# ANA_FE_CLK_SYNTH.net
KiCad netlist of a schematic drawn in Altium Designer
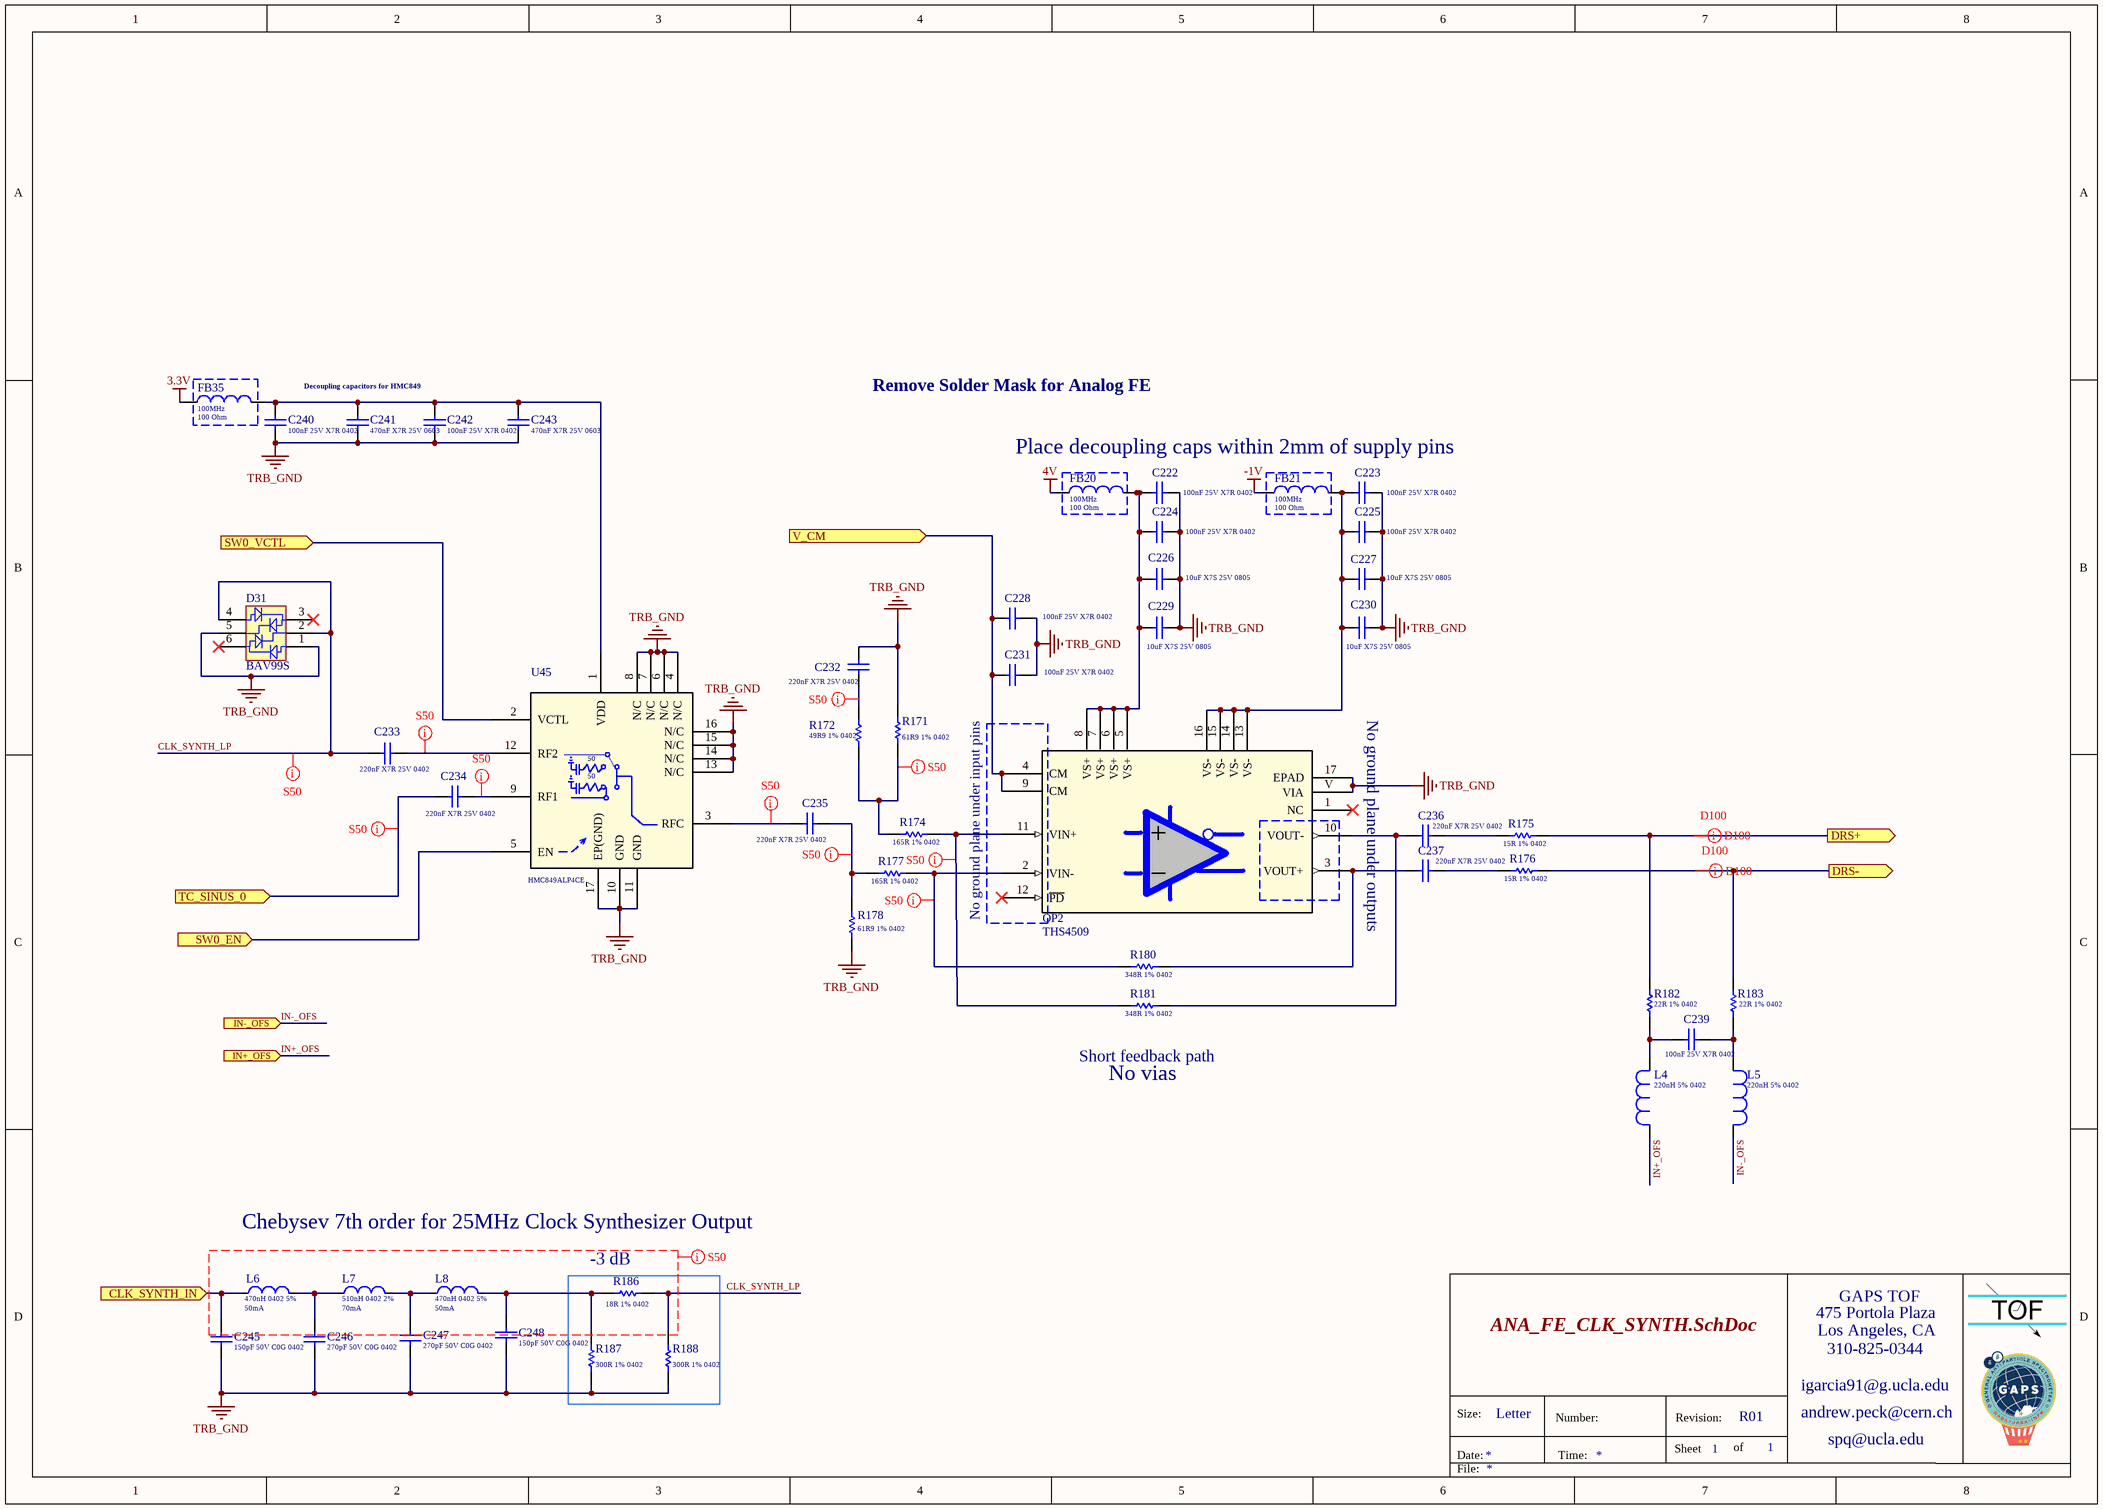
[diagram p0: ANA_FE_CLK_SYNTH.SchDoc]

(export (version "E")
  (design (tool "Eeschema 10.0.6"))
  (components
    (comp (ref "C222")
      (value "Cap_Taiyo_Yuden_TMK105B7104KV-FR_100nF")
      (footprint "Cap_Taiyo_Yuden_TMK105B7104KV-FR_100nF")
      (description "CAP CER 100nF 25V X7R 0402")
      (fields (field (name "CAPACITANCE") "100nF 25V X7R 0402"))
      (libsource (lib "Cap_Taiyo_Yuden_TMK105B7104KV-FR_100nF") (part "Cap_Taiyo_Yuden_TMK105B7104KV-FR_100nF"))
    )
    (comp (ref "C223")
      (value "Cap_Taiyo_Yuden_TMK105B7104KV-FR_100nF")
      (footprint "Cap_Taiyo_Yuden_TMK105B7104KV-FR_100nF")
      (description "CAP CER 100nF 25V X7R 0402")
      (fields (field (name "CAPACITANCE") "100nF 25V X7R 0402"))
      (libsource (lib "Cap_Taiyo_Yuden_TMK105B7104KV-FR_100nF") (part "Cap_Taiyo_Yuden_TMK105B7104KV-FR_100nF"))
    )
    (comp (ref "C224")
      (value "Cap_Taiyo_Yuden_TMK105B7104KV-FR_100nF")
      (footprint "Cap_Taiyo_Yuden_TMK105B7104KV-FR_100nF")
      (description "CAP CER 100nF 25V X7R 0402")
      (fields (field (name "CAPACITANCE") "100nF 25V X7R 0402"))
      (libsource (lib "Cap_Taiyo_Yuden_TMK105B7104KV-FR_100nF") (part "Cap_Taiyo_Yuden_TMK105B7104KV-FR_100nF"))
    )
    (comp (ref "C225")
      (value "Cap_Taiyo_Yuden_TMK105B7104KV-FR_100nF")
      (footprint "Cap_Taiyo_Yuden_TMK105B7104KV-FR_100nF")
      (description "CAP CER 100nF 25V X7R 0402")
      (fields (field (name "CAPACITANCE") "100nF 25V X7R 0402"))
      (libsource (lib "Cap_Taiyo_Yuden_TMK105B7104KV-FR_100nF") (part "Cap_Taiyo_Yuden_TMK105B7104KV-FR_100nF"))
    )
    (comp (ref "C226")
      (value "Cap_Murata_ GRM21BC71E106ME11L_10uF")
      (footprint "Cap_Murata_ GRM21BC71E106ME11L_10uF")
      (description "CAP CER 10uF 25V X7R 0805")
      (fields (field (name "CAPACITANCE") "10uF X7S 25V 0805"))
      (libsource (lib "Cap_Murata_ GRM21BC71E106ME11L_10uF") (part "Cap_Murata_ GRM21BC71E106ME11L_10uF"))
    )
    (comp (ref "C227")
      (value "Cap_Murata_ GRM21BC71E106ME11L_10uF")
      (footprint "Cap_Murata_ GRM21BC71E106ME11L_10uF")
      (description "CAP CER 10uF 25V X7R 0805")
      (fields (field (name "CAPACITANCE") "10uF X7S 25V 0805"))
      (libsource (lib "Cap_Murata_ GRM21BC71E106ME11L_10uF") (part "Cap_Murata_ GRM21BC71E106ME11L_10uF"))
    )
    (comp (ref "C228")
      (value "Cap_Taiyo_Yuden_TMK105B7104KV-FR_100nF")
      (footprint "Cap_Taiyo_Yuden_TMK105B7104KV-FR_100nF")
      (description "CAP CER 100nF 25V X7R 0402")
      (fields (field (name "CAPACITANCE") "100nF 25V X7R 0402"))
      (libsource (lib "Cap_Taiyo_Yuden_TMK105B7104KV-FR_100nF") (part "Cap_Taiyo_Yuden_TMK105B7104KV-FR_100nF"))
    )
    (comp (ref "C229")
      (value "Cap_Murata_ GRM21BC71E106ME11L_10uF")
      (footprint "Cap_Murata_ GRM21BC71E106ME11L_10uF")
      (description "CAP CER 10uF 25V X7R 0805")
      (fields (field (name "CAPACITANCE") "10uF X7S 25V 0805"))
      (libsource (lib "Cap_Murata_ GRM21BC71E106ME11L_10uF") (part "Cap_Murata_ GRM21BC71E106ME11L_10uF"))
    )
    (comp (ref "C230")
      (value "Cap_Murata_ GRM21BC71E106ME11L_10uF")
      (footprint "Cap_Murata_ GRM21BC71E106ME11L_10uF")
      (description "CAP CER 10uF 25V X7R 0805")
      (fields (field (name "CAPACITANCE") "10uF X7S 25V 0805"))
      (libsource (lib "Cap_Murata_ GRM21BC71E106ME11L_10uF") (part "Cap_Murata_ GRM21BC71E106ME11L_10uF"))
    )
    (comp (ref "C231")
      (value "Cap_Taiyo_Yuden_TMK105B7104KV-FR_100nF")
      (footprint "Cap_Taiyo_Yuden_TMK105B7104KV-FR_100nF")
      (description "CAP CER 100nF 25V X7R 0402")
      (fields (field (name "CAPACITANCE") "100nF 25V X7R 0402"))
      (libsource (lib "Cap_Taiyo_Yuden_TMK105B7104KV-FR_100nF") (part "Cap_Taiyo_Yuden_TMK105B7104KV-FR_100nF"))
    )
    (comp (ref "C232")
      (value "Cap_TDK_C1608X5R1A106M080AC_220nF")
      (footprint "Cap_TDK_C1608X5R1A106M080AC_220nF")
      (description "CAP CER 220nF 50V X7R 0402")
      (fields (field (name "CAPACITANCE") "220nF X7R 25V 0402"))
      (libsource (lib "Cap_TDK_C1608X5R1A106M080AC_220nF") (part "Cap_TDK_C1608X5R1A106M080AC_220nF"))
    )
    (comp (ref "C233")
      (value "Cap_TDK_C1608X5R1A106M080AC_220nF")
      (footprint "Cap_TDK_C1608X5R1A106M080AC_220nF")
      (description "CAP CER 220nF 50V X7R 0402")
      (fields (field (name "CAPACITANCE") "220nF X7R 25V 0402"))
      (libsource (lib "Cap_TDK_C1608X5R1A106M080AC_220nF") (part "Cap_TDK_C1608X5R1A106M080AC_220nF"))
    )
    (comp (ref "C234")
      (value "Cap_TDK_C1608X5R1A106M080AC_220nF")
      (footprint "Cap_TDK_C1608X5R1A106M080AC_220nF")
      (description "CAP CER 220nF 50V X7R 0402")
      (fields (field (name "CAPACITANCE") "220nF X7R 25V 0402"))
      (libsource (lib "Cap_TDK_C1608X5R1A106M080AC_220nF") (part "Cap_TDK_C1608X5R1A106M080AC_220nF"))
    )
    (comp (ref "C235")
      (value "Cap_TDK_C1608X5R1A106M080AC_220nF")
      (footprint "Cap_TDK_C1608X5R1A106M080AC_220nF")
      (description "CAP CER 220nF 50V X7R 0402")
      (fields (field (name "CAPACITANCE") "220nF X7R 25V 0402"))
      (libsource (lib "Cap_TDK_C1608X5R1A106M080AC_220nF") (part "Cap_TDK_C1608X5R1A106M080AC_220nF"))
    )
    (comp (ref "C236")
      (value "Cap_TDK_C1608X5R1A106M080AC_220nF")
      (footprint "Cap_TDK_C1608X5R1A106M080AC_220nF")
      (description "CAP CER 220nF 50V X7R 0402")
      (fields (field (name "CAPACITANCE") "220nF X7R 25V 0402"))
      (libsource (lib "Cap_TDK_C1608X5R1A106M080AC_220nF") (part "Cap_TDK_C1608X5R1A106M080AC_220nF"))
    )
    (comp (ref "C237")
      (value "Cap_TDK_C1608X5R1A106M080AC_220nF")
      (footprint "Cap_TDK_C1608X5R1A106M080AC_220nF")
      (description "CAP CER 220nF 50V X7R 0402")
      (fields (field (name "CAPACITANCE") "220nF X7R 25V 0402"))
      (libsource (lib "Cap_TDK_C1608X5R1A106M080AC_220nF") (part "Cap_TDK_C1608X5R1A106M080AC_220nF"))
    )
    (comp (ref "C239")
      (value "Cap_Taiyo_Yuden_TMK105B7104KV-FR_100nF")
      (footprint "Cap_Taiyo_Yuden_TMK105B7104KV-FR_100nF")
      (description "CAP CER 100nF 25V X7R 0402")
      (fields (field (name "CAPACITANCE") "100nF 25V X7R 0402"))
      (libsource (lib "Cap_Taiyo_Yuden_TMK105B7104KV-FR_100nF") (part "Cap_Taiyo_Yuden_TMK105B7104KV-FR_100nF"))
    )
    (comp (ref "C240")
      (value "Cap_Taiyo_Yuden_TMK105B7104KV-FR_100nF")
      (footprint "Cap_Taiyo_Yuden_TMK105B7104KV-FR_100nF")
      (description "CAP CER 100nF 25V X7R 0402")
      (fields (field (name "CAPACITANCE") "100nF 25V X7R 0402"))
      (libsource (lib "Cap_Taiyo_Yuden_TMK105B7104KV-FR_100nF") (part "Cap_Taiyo_Yuden_TMK105B7104KV-FR_100nF"))
    )
    (comp (ref "C241")
      (value "Cap_Wurth_Electronics_885012206075_470nF")
      (footprint "Cap_Wurth_Electronics_885012206075_470nF")
      (description "CAP CER 470nF 25V X7R 0603")
      (fields (field (name "CAPACITANCE") "470nF X7R 25V 0603"))
      (libsource (lib "Cap_Wurth_Electronics_885012206075_470nF") (part "Cap_Wurth_Electronics_885012206075_470nF"))
    )
    (comp (ref "C242")
      (value "Cap_Taiyo_Yuden_TMK105B7104KV-FR_100nF")
      (footprint "Cap_Taiyo_Yuden_TMK105B7104KV-FR_100nF")
      (description "CAP CER 100nF 25V X7R 0402")
      (fields (field (name "CAPACITANCE") "100nF 25V X7R 0402"))
      (libsource (lib "Cap_Taiyo_Yuden_TMK105B7104KV-FR_100nF") (part "Cap_Taiyo_Yuden_TMK105B7104KV-FR_100nF"))
    )
    (comp (ref "C243")
      (value "Cap_Wurth_Electronics_885012206075_470nF")
      (footprint "Cap_Wurth_Electronics_885012206075_470nF")
      (description "CAP CER 470nF 25V X7R 0603")
      (fields (field (name "CAPACITANCE") "470nF X7R 25V 0603"))
      (libsource (lib "Cap_Wurth_Electronics_885012206075_470nF") (part "Cap_Wurth_Electronics_885012206075_470nF"))
    )
    (comp (ref "C245")
      (value "Cap_TDK_CGA2B2C0G2A151J050BE_150pF")
      (footprint "Cap_TDK_CGA2B2C0G2A151J050BE_150pF")
      (description "CAP 150pF 50V C0G ±1% 0402 (1000 Metric) Thickness 1mm SMD")
      (fields (field (name "CAPACITANCE") "150pF 50V C0G 0402"))
      (libsource (lib "Cap_TDK_CGA2B2C0G2A151J050BE_150pF") (part "Cap_TDK_CGA2B2C0G2A151J050BE_150pF"))
    )
    (comp (ref "C246")
      (value "Cap_Murata_GCM1555C1H271FA16D_270pF")
      (footprint "Cap_Murata_GCM1555C1H271FA16D_270pF")
      (description "CAP 270pF 50V C0G ±1% 0402")
      (fields (field (name "CAPACITANCE") "270pF 50V C0G 0402"))
      (libsource (lib "Cap_Murata_GCM1555C1H271FA16D_270pF") (part "Cap_Murata_GCM1555C1H271FA16D_270pF"))
    )
    (comp (ref "C247")
      (value "Cap_Murata_GCM1555C1H271FA16D_270pF")
      (footprint "Cap_Murata_GCM1555C1H271FA16D_270pF")
      (description "CAP 270pF 50V C0G ±1% 0402")
      (fields (field (name "CAPACITANCE") "270pF 50V C0G 0402"))
      (libsource (lib "Cap_Murata_GCM1555C1H271FA16D_270pF") (part "Cap_Murata_GCM1555C1H271FA16D_270pF"))
    )
    (comp (ref "C248")
      (value "Cap_TDK_CGA2B2C0G2A151J050BE_150pF")
      (footprint "Cap_TDK_CGA2B2C0G2A151J050BE_150pF")
      (description "CAP 150pF 50V C0G ±1% 0402 (1000 Metric) Thickness 1mm SMD")
      (fields (field (name "CAPACITANCE") "150pF 50V C0G 0402"))
      (libsource (lib "Cap_TDK_CGA2B2C0G2A151J050BE_150pF") (part "Cap_TDK_CGA2B2C0G2A151J050BE_150pF"))
    )
    (comp (ref "D31")
      (value "BAV99S")
      (footprint "INF-SOT363_V")
      (description "Silicon Switching Diode, SOT363, Reel, Green")
      (fields (field (name "MANUFACTURER") "Infineon"))
      (libsource (lib "Altium Content Vault") (part "INF-D_A1K2C3A4K5C6-6"))
    )
    (comp (ref "FB20")
      (value "742792731")
      (footprint "FB_Wurth_Electronics_742792731_100Ohms")
      (description "FB SMD 100 OHM 25% 1.2A 0402")
      (fields (field (name "MEASURING FREQUENCY") "100MHz") (field (name "IMPEDANCE") "100 Ohm"))
      (libsource (lib "FB_Wurth_Electronics_742792731_100Ohms") (part "FB_Wurth_Electronics_742792731_100Ohms"))
    )
    (comp (ref "FB21")
      (value "742792731")
      (footprint "FB_Wurth_Electronics_742792731_100Ohms")
      (description "FB SMD 100 OHM 25% 1.2A 0402")
      (fields (field (name "MEASURING FREQUENCY") "100MHz") (field (name "IMPEDANCE") "100 Ohm"))
      (libsource (lib "FB_Wurth_Electronics_742792731_100Ohms") (part "FB_Wurth_Electronics_742792731_100Ohms"))
    )
    (comp (ref "FB35")
      (value "742792731")
      (footprint "FB_Wurth_Electronics_742792731_100Ohms")
      (description "FB SMD 100 OHM 25% 1.2A 0402")
      (fields (field (name "MEASURING FREQUENCY") "100MHz") (field (name "IMPEDANCE") "100 Ohm"))
      (libsource (lib "FB_Wurth_Electronics_742792731_100Ohms") (part "FB_Wurth_Electronics_742792731_100Ohms"))
    )
    (comp (ref "L4")
      (value "Ind_TDK_ MLG1005SR22JT000_220nH")
      (footprint "Ind_TDK_ MLG1005SR22JT000_220nH")
      (description "Fixed Inductors .22 UH 5%")
      (fields (field (name "INDUCTANCE") "220nH 5% 0402"))
      (libsource (lib "Ind_TDK_ MLG1005SR22JT000_220nH") (part "Ind_TDK_ MLG1005SR22JT000_220nH"))
    )
    (comp (ref "L5")
      (value "Ind_TDK_ MLG1005SR22JT000_220nH")
      (footprint "Ind_TDK_ MLG1005SR22JT000_220nH")
      (description "Fixed Inductors .22 UH 5%")
      (fields (field (name "INDUCTANCE") "220nH 5% 0402"))
      (libsource (lib "Ind_TDK_ MLG1005SR22JT000_220nH") (part "Ind_TDK_ MLG1005SR22JT000_220nH"))
    )
    (comp (ref "L6")
      (value "470nH 0402 5%")
      (footprint "TDK_MLF1005GR47JT000_0")
      (description "IND 470nH Shielded Multilayer Inductor 50mA 420 mOhm Max 0402 (1005 Metric)")
      (fields
        (field (name "PART NUMBER") "MLF1005GR47JT000")
        (field (name "MANUFACTURER") "TDK")
        (field (name "CURRENT RATING") "50mA")
      )
      (libsource (lib "Ind_TDK_MLF1005GR47JT000_470nH") (part "Ind_TDK_MLF1005GR47JT000"))
    )
    (comp (ref "L7")
      (value "510nH 0402 2%")
      (footprint "TDK_MHQ1005PR51GT000_0")
      (description "IND 510nH Shielded Multilayer Inductor 70mA 10.2 Ohm Max 0402 (1005 Metric)")
      (fields
        (field (name "PART NUMBER") "MHQ1005PR51GT000")
        (field (name "MANUFACTURER") "TDK")
        (field (name "CURRENT RATING") "70mA")
      )
      (libsource (lib "Ind_TDK_MHQ1005PR51GT000_510nH") (part "Ind_TDK_MHQ1005PR51GT000"))
    )
    (comp (ref "L8")
      (value "470nH 0402 5%")
      (footprint "TDK_MLF1005GR47JT000_0")
      (description "IND 470nH Shielded Multilayer Inductor 50mA 420 mOhm Max 0402 (1005 Metric)")
      (fields
        (field (name "PART NUMBER") "MLF1005GR47JT000")
        (field (name "MANUFACTURER") "TDK")
        (field (name "CURRENT RATING") "50mA")
      )
      (libsource (lib "Ind_TDK_MLF1005GR47JT000_470nH") (part "Ind_TDK_MLF1005GR47JT000"))
    )
    (comp (ref "OP2")
      (value "THS4509")
      (footprint "RGT16")
      (description "Imported")
      (fields (field (name "MANUFACTURER_PART_NUMBER") "THS4509RGTT"))
      (libsource (lib "THS4509RGTT") (part "THS4509RGTT"))
    )
    (comp (ref "R171")
      (value "61R9 1% 0402")
      (footprint "RESC0402(1005)_L")
      (description "61R9 0.063W 1% 0402 (1005 Metric)  SMD")
      (fields (field (name "TOLERANCE") "1 %") (field (name "POWER") "0.063 W"))
      (libsource (lib "Altium Content Vault") (part "RES"))
    )
    (comp (ref "R172")
      (value "49R9 1% 0402")
      (footprint "RESC0402(1005)_L")
      (description "49R9 0.063W 1% 0402 (1005 Metric)  SMD")
      (fields (field (name "POWER") "0.063 W") (field (name "TOLERANCE") "1 %"))
      (libsource (lib "Altium Content Vault") (part "RES"))
    )
    (comp (ref "R174")
      (value "165R 1% 0402")
      (footprint "RESC0402(1005)_L")
      (description "165R 0.063W 1% 0402 (1005 Metric)  SMD")
      (fields (field (name "POWER") "0.063 W") (field (name "TOLERANCE") "1 %"))
      (libsource (lib "Altium Content Vault") (part "RES"))
    )
    (comp (ref "R175")
      (value "15R 1% 0402")
      (footprint "RESC0402(1005)_L")
      (description "15R 0.063W 1% 0402 (1005 Metric)  SMD")
      (fields (field (name "TOLERANCE") "1 %") (field (name "POWER") "0.063 W"))
      (libsource (lib "Altium Content Vault") (part "RES"))
    )
    (comp (ref "R176")
      (value "15R 1% 0402")
      (footprint "RESC0402(1005)_L")
      (description "15R 0.063W 1% 0402 (1005 Metric)  SMD")
      (fields (field (name "TOLERANCE") "1 %") (field (name "POWER") "0.063 W"))
      (libsource (lib "Altium Content Vault") (part "RES"))
    )
    (comp (ref "R177")
      (value "165R 1% 0402")
      (footprint "RESC0402(1005)_L")
      (description "165R 0.063W 1% 0402 (1005 Metric)  SMD")
      (fields (field (name "POWER") "0.063 W") (field (name "TOLERANCE") "1 %"))
      (libsource (lib "Altium Content Vault") (part "RES"))
    )
    (comp (ref "R178")
      (value "61R9 1% 0402")
      (footprint "RESC0402(1005)_L")
      (description "61R9 0.063W 1% 0402 (1005 Metric)  SMD")
      (fields (field (name "TOLERANCE") "1 %") (field (name "POWER") "0.063 W"))
      (libsource (lib "Altium Content Vault") (part "RES"))
    )
    (comp (ref "R180")
      (value "348R 1% 0402")
      (footprint "RESC0402(1005)_L")
      (description "348R 0.063W 1% 0402 (1005 Metric)  SMD")
      (fields (field (name "TOLERANCE") "1 %") (field (name "POWER") "0.063 W"))
      (libsource (lib "Altium Content Vault") (part "RES"))
    )
    (comp (ref "R181")
      (value "348R 1% 0402")
      (footprint "RESC0402(1005)_L")
      (description "348R 0.063W 1% 0402 (1005 Metric)  SMD")
      (fields (field (name "TOLERANCE") "1 %") (field (name "POWER") "0.063 W"))
      (libsource (lib "Altium Content Vault") (part "RES"))
    )
    (comp (ref "R182")
      (value "22R 1% 0402")
      (footprint "RESC0402(1005)_L")
      (description "22R 0.063W 1% 0402 (1005 Metric)  SMD")
      (fields (field (name "TOLERANCE") "1 %") (field (name "POWER") "0.063 W"))
      (libsource (lib "Altium Content Vault") (part "RES"))
    )
    (comp (ref "R183")
      (value "22R 1% 0402")
      (footprint "RESC0402(1005)_L")
      (description "22R 0.063W 1% 0402 (1005 Metric)  SMD")
      (fields (field (name "TOLERANCE") "1 %") (field (name "POWER") "0.063 W"))
      (libsource (lib "Altium Content Vault") (part "RES"))
    )
    (comp (ref "R186")
      (value "18R 1% 0402")
      (footprint "RESC0402(1005)_L")
      (description "18R 0.063W 1% 0402 (1005 Metric)  SMD")
      (fields (field (name "TOLERANCE") "1 %") (field (name "POWER") "0.063 W"))
      (libsource (lib "Altium Content Vault") (part "RES"))
    )
    (comp (ref "R187")
      (value "300R 1% 0402")
      (footprint "RESC0402(1005)_L")
      (description "300R 0.063W 1% 0402 (1005 Metric)  SMD")
      (fields (field (name "TOLERANCE") "1 %") (field (name "POWER") "0.063 W"))
      (libsource (lib "Altium Content Vault") (part "RES"))
    )
    (comp (ref "R188")
      (value "300R 1% 0402")
      (footprint "RESC0402(1005)_L")
      (description "300R 0.063W 1% 0402 (1005 Metric)  SMD")
      (fields (field (name "TOLERANCE") "1 %") (field (name "POWER") "0.063 W"))
      (libsource (lib "Altium Content Vault") (part "RES"))
    )
    (comp (ref "U45")
      (value "HMC849")
      (footprint "CP_16_40")
      (description "RF Switch ICs DC-6 GHZ Hi Isolation Switch")
      (fields (field (name "MANUFACTURER_PART_NUMBER") "HMC849ALP4CE") (field (name "SERIES") "HMC849ALP4CE"))
      (libsource (lib "HMC849ALP4CE") (part "HMC849ALP4CE"))
    )
  )
  (nets
    (net (code "1") (name "-1V") (class "Default")
      (node (ref "FB21") (pin "1") (pinfunction "1_1") (pintype "passive"))
    )
    (net (code "2") (name "/CLK_SYNTH_IN") (class "Default")
      (node (ref "C245") (pin "2") (pinfunction "2_2") (pintype "passive"))
      (node (ref "L6") (pin "1") (pinfunction "1_1") (pintype "passive"))
    )
    (net (code "3") (name "/CLK_SYNTH_LP") (class "Default")
      (node (ref "C233") (pin "2") (pinfunction "2_2") (pintype "passive"))
      (node (ref "D31") (pin "2") (pinfunction "K2_2") (pintype "passive"))
      (node (ref "D31") (pin "4") (pinfunction "A4_4") (pintype "passive"))
      (node (ref "R186") (pin "2") (pinfunction "2_2") (pintype "passive"))
      (node (ref "R188") (pin "2") (pinfunction "2_2") (pintype "passive"))
    )
    (net (code "4") (name "/DRS+") (class "Default")
      (node (ref "R175") (pin "2") (pinfunction "2_2") (pintype "passive"))
      (node (ref "R182") (pin "2") (pinfunction "2_2") (pintype "passive"))
    )
    (net (code "5") (name "/DRS-") (class "Default")
      (node (ref "R176") (pin "2") (pinfunction "2_2") (pintype "passive"))
      (node (ref "R183") (pin "2") (pinfunction "2_2") (pintype "passive"))
    )
    (net (code "6") (name "/IN+_OFS") (class "Default")
      (node (ref "L4") (pin "2") (pinfunction "2_2") (pintype "passive"))
    )
    (net (code "7") (name "/IN-_OFS") (class "Default")
      (node (ref "L5") (pin "1") (pinfunction "1_1") (pintype "passive"))
    )
    (net (code "8") (name "/SW0_EN") (class "Default")
      (node (ref "U45") (pin "5") (pinfunction "EN_5") (pintype "passive"))
    )
    (net (code "9") (name "/SW0_VCTL") (class "Default")
      (node (ref "U45") (pin "2") (pinfunction "VCTL_2") (pintype "passive"))
    )
    (net (code "10") (name "/TC_SINUS_0") (class "Default")
      (node (ref "C234") (pin "2") (pinfunction "2_2") (pintype "passive"))
    )
    (net (code "11") (name "/V_CM") (class "Default")
      (node (ref "C228") (pin "1") (pinfunction "1_1") (pintype "passive"))
      (node (ref "C231") (pin "1") (pinfunction "1_1") (pintype "passive"))
      (node (ref "OP2") (pin "4") (pinfunction "CM_4") (pintype "passive"))
      (node (ref "OP2") (pin "9") (pinfunction "CM_9") (pintype "passive"))
    )
    (net (code "12") (name "3.3V") (class "Default")
      (node (ref "FB35") (pin "1") (pinfunction "1_1") (pintype "passive"))
    )
    (net (code "13") (name "4V") (class "Default")
      (node (ref "FB20") (pin "1") (pinfunction "1_1") (pintype "passive"))
    )
    (net (code "14") (name "Net-(C222-Pad1)") (class "Default")
      (node (ref "C222") (pin "1") (pinfunction "1_1") (pintype "passive"))
      (node (ref "C224") (pin "1") (pinfunction "1_1") (pintype "passive"))
      (node (ref "C226") (pin "2") (pinfunction "2_2") (pintype "passive"))
      (node (ref "C229") (pin "2") (pinfunction "2_2") (pintype "passive"))
      (node (ref "FB20") (pin "2") (pinfunction "2_2") (pintype "passive"))
      (node (ref "OP2") (pin "5") (pinfunction "VS+_5") (pintype "power_in"))
      (node (ref "OP2") (pin "6") (pinfunction "VS+_6") (pintype "power_in"))
      (node (ref "OP2") (pin "7") (pinfunction "VS+_7") (pintype "power_in"))
      (node (ref "OP2") (pin "8") (pinfunction "VS+_8") (pintype "power_in"))
    )
    (net (code "15") (name "Net-(C223-Pad1)") (class "Default")
      (node (ref "C223") (pin "1") (pinfunction "1_1") (pintype "passive"))
      (node (ref "C225") (pin "1") (pinfunction "1_1") (pintype "passive"))
      (node (ref "C227") (pin "2") (pinfunction "2_2") (pintype "passive"))
      (node (ref "C230") (pin "2") (pinfunction "2_2") (pintype "passive"))
      (node (ref "FB21") (pin "2") (pinfunction "2_2") (pintype "passive"))
      (node (ref "OP2") (pin "13") (pinfunction "VS-_13") (pintype "power_in"))
      (node (ref "OP2") (pin "14") (pinfunction "VS-_14") (pintype "power_in"))
      (node (ref "OP2") (pin "15") (pinfunction "VS-_15") (pintype "power_in"))
      (node (ref "OP2") (pin "16") (pinfunction "VS-_16") (pintype "power_in"))
    )
    (net (code "16") (name "Net-(C232-Pad2)") (class "Default")
      (node (ref "C232") (pin "2") (pinfunction "2_2") (pintype "passive"))
      (node (ref "R172") (pin "2") (pinfunction "2_2") (pintype "passive"))
    )
    (net (code "17") (name "Net-(C235-Pad1)") (class "Default")
      (node (ref "C235") (pin "1") (pinfunction "1_1") (pintype "passive"))
      (node (ref "R177") (pin "1") (pinfunction "1_1") (pintype "passive"))
      (node (ref "R178") (pin "2") (pinfunction "2_2") (pintype "passive"))
    )
    (net (code "18") (name "Net-(C236-Pad1)") (class "Default")
      (node (ref "C236") (pin "1") (pinfunction "1_1") (pintype "passive"))
      (node (ref "R175") (pin "1") (pinfunction "1_1") (pintype "passive"))
    )
    (net (code "19") (name "Net-(C237-Pad1)") (class "Default")
      (node (ref "C237") (pin "1") (pinfunction "1_1") (pintype "passive"))
      (node (ref "R176") (pin "1") (pinfunction "1_1") (pintype "passive"))
    )
    (net (code "20") (name "Net-(C239-Pad1)") (class "Default")
      (node (ref "C239") (pin "1") (pinfunction "1_1") (pintype "passive"))
      (node (ref "L4") (pin "1") (pinfunction "1_1") (pintype "passive"))
      (node (ref "R182") (pin "1") (pinfunction "1_1") (pintype "passive"))
    )
    (net (code "21") (name "Net-(C239-Pad2)") (class "Default")
      (node (ref "C239") (pin "2") (pinfunction "2_2") (pintype "passive"))
      (node (ref "L5") (pin "2") (pinfunction "2_2") (pintype "passive"))
      (node (ref "R183") (pin "1") (pinfunction "1_1") (pintype "passive"))
    )
    (net (code "22") (name "Net-(C246-Pad2)") (class "Default")
      (node (ref "C246") (pin "2") (pinfunction "2_2") (pintype "passive"))
      (node (ref "L6") (pin "2") (pinfunction "2_2") (pintype "passive"))
      (node (ref "L7") (pin "1") (pinfunction "1_1") (pintype "passive"))
    )
    (net (code "23") (name "Net-(C247-Pad2)") (class "Default")
      (node (ref "C247") (pin "2") (pinfunction "2_2") (pintype "passive"))
      (node (ref "L7") (pin "2") (pinfunction "2_2") (pintype "passive"))
      (node (ref "L8") (pin "1") (pinfunction "1_1") (pintype "passive"))
    )
    (net (code "24") (name "Net-(C248-Pad2)") (class "Default")
      (node (ref "C248") (pin "2") (pinfunction "2_2") (pintype "passive"))
      (node (ref "L8") (pin "2") (pinfunction "2_2") (pintype "passive"))
      (node (ref "R186") (pin "1") (pinfunction "1_1") (pintype "passive"))
      (node (ref "R187") (pin "2") (pinfunction "2_2") (pintype "passive"))
    )
    (net (code "25") (name "Net-(OP2-VIN+)") (class "Default")
      (node (ref "OP2") (pin "11") (pinfunction "VIN+_11") (pintype "input"))
      (node (ref "R174") (pin "2") (pinfunction "2_2") (pintype "passive"))
      (node (ref "R181") (pin "1") (pinfunction "1_1") (pintype "passive"))
    )
    (net (code "26") (name "Net-(OP2-VIN-)") (class "Default")
      (node (ref "OP2") (pin "2") (pinfunction "VIN-_2") (pintype "input"))
      (node (ref "R177") (pin "2") (pinfunction "2_2") (pintype "passive"))
      (node (ref "R180") (pin "1") (pinfunction "1_1") (pintype "passive"))
    )
    (net (code "27") (name "Net-(OP2-VOUT+)") (class "Default")
      (node (ref "C237") (pin "2") (pinfunction "2_2") (pintype "passive"))
      (node (ref "OP2") (pin "3") (pinfunction "VOUT+_3") (pintype "output"))
      (node (ref "R180") (pin "2") (pinfunction "2_2") (pintype "passive"))
    )
    (net (code "28") (name "Net-(OP2-VOUT-)") (class "Default")
      (node (ref "C236") (pin "2") (pinfunction "2_2") (pintype "passive"))
      (node (ref "OP2") (pin "10") (pinfunction "VOUT-_10") (pintype "output"))
      (node (ref "R181") (pin "2") (pinfunction "2_2") (pintype "passive"))
    )
    (net (code "29") (name "Net-(R171-Pad1)") (class "Default")
      (node (ref "R171") (pin "1") (pinfunction "1_1") (pintype "passive"))
      (node (ref "R172") (pin "1") (pinfunction "1_1") (pintype "passive"))
      (node (ref "R174") (pin "1") (pinfunction "1_1") (pintype "passive"))
    )
    (net (code "30") (name "Net-(U45-RF1)") (class "Default")
      (node (ref "C234") (pin "1") (pinfunction "1_1") (pintype "passive"))
      (node (ref "U45") (pin "9") (pinfunction "RF1_9") (pintype "passive"))
    )
    (net (code "31") (name "Net-(U45-RF2)") (class "Default")
      (node (ref "C233") (pin "1") (pinfunction "1_1") (pintype "passive"))
      (node (ref "U45") (pin "12") (pinfunction "RF2_12") (pintype "passive"))
    )
    (net (code "32") (name "Net-(U45-RFC)") (class "Default")
      (node (ref "C235") (pin "2") (pinfunction "2_2") (pintype "passive"))
      (node (ref "U45") (pin "3") (pinfunction "RFC_3") (pintype "passive"))
    )
    (net (code "33") (name "Net-(U45-VDD)") (class "Default")
      (node (ref "C240") (pin "2") (pinfunction "2_2") (pintype "passive"))
      (node (ref "C241") (pin "1") (pinfunction "1_1") (pintype "passive"))
      (node (ref "C242") (pin "2") (pinfunction "2_2") (pintype "passive"))
      (node (ref "C243") (pin "1") (pinfunction "1_1") (pintype "passive"))
      (node (ref "FB35") (pin "2") (pinfunction "2_2") (pintype "passive"))
      (node (ref "U45") (pin "1") (pinfunction "VDD_1") (pintype "passive"))
    )
    (net (code "34") (name "TRB_GND") (class "Default")
      (node (ref "C222") (pin "2") (pinfunction "2_2") (pintype "passive"))
      (node (ref "C223") (pin "2") (pinfunction "2_2") (pintype "passive"))
      (node (ref "C224") (pin "2") (pinfunction "2_2") (pintype "passive"))
      (node (ref "C225") (pin "2") (pinfunction "2_2") (pintype "passive"))
      (node (ref "C226") (pin "1") (pinfunction "1_1") (pintype "passive"))
      (node (ref "C227") (pin "1") (pinfunction "1_1") (pintype "passive"))
      (node (ref "C228") (pin "2") (pinfunction "2_2") (pintype "passive"))
      (node (ref "C229") (pin "1") (pinfunction "1_1") (pintype "passive"))
      (node (ref "C230") (pin "1") (pinfunction "1_1") (pintype "passive"))
      (node (ref "C231") (pin "2") (pinfunction "2_2") (pintype "passive"))
      (node (ref "C232") (pin "1") (pinfunction "1_1") (pintype "passive"))
      (node (ref "C240") (pin "1") (pinfunction "1_1") (pintype "passive"))
      (node (ref "C241") (pin "2") (pinfunction "2_2") (pintype "passive"))
      (node (ref "C242") (pin "1") (pinfunction "1_1") (pintype "passive"))
      (node (ref "C243") (pin "2") (pinfunction "2_2") (pintype "passive"))
      (node (ref "C245") (pin "1") (pinfunction "1_1") (pintype "passive"))
      (node (ref "C246") (pin "1") (pinfunction "1_1") (pintype "passive"))
      (node (ref "C247") (pin "1") (pinfunction "1_1") (pintype "passive"))
      (node (ref "C248") (pin "1") (pinfunction "1_1") (pintype "passive"))
      (node (ref "D31") (pin "1") (pinfunction "A1_1") (pintype "passive"))
      (node (ref "D31") (pin "5") (pinfunction "K5_5") (pintype "passive"))
      (node (ref "OP2") (pin "17") (pinfunction "EPAD_17") (pintype "passive"))
      (node (ref "OP2") (pin "V") (pinfunction "VIA_V") (pintype "passive"))
      (node (ref "R171") (pin "2") (pinfunction "2_2") (pintype "passive"))
      (node (ref "R178") (pin "1") (pinfunction "1_1") (pintype "passive"))
      (node (ref "R187") (pin "1") (pinfunction "1_1") (pintype "passive"))
      (node (ref "R188") (pin "1") (pinfunction "1_1") (pintype "passive"))
      (node (ref "U45") (pin "10") (pinfunction "GND_10") (pintype "passive"))
      (node (ref "U45") (pin "11") (pinfunction "GND_11") (pintype "passive"))
      (node (ref "U45") (pin "13") (pinfunction "N/C_13") (pintype "passive"))
      (node (ref "U45") (pin "14") (pinfunction "N/C_14") (pintype "passive"))
      (node (ref "U45") (pin "15") (pinfunction "N/C_15") (pintype "passive"))
      (node (ref "U45") (pin "16") (pinfunction "N/C_16") (pintype "passive"))
      (node (ref "U45") (pin "17") (pinfunction "EP(GND)_17") (pintype "passive"))
      (node (ref "U45") (pin "4") (pinfunction "N/C_4") (pintype "passive"))
      (node (ref "U45") (pin "6") (pinfunction "N/C_6") (pintype "passive"))
      (node (ref "U45") (pin "7") (pinfunction "N/C_7") (pintype "passive"))
      (node (ref "U45") (pin "8") (pinfunction "N/C_8") (pintype "passive"))
    )
    (net (code "35") (name "unconnected-(D31-C3-Pad3)") (class "Default")
      (node (ref "D31") (pin "3") (pinfunction "C3_3") (pintype "passive+no_connect"))
    )
    (net (code "36") (name "unconnected-(D31-C6-Pad6)") (class "Default")
      (node (ref "D31") (pin "6") (pinfunction "C6_6") (pintype "passive+no_connect"))
    )
    (net (code "37") (name "unconnected-(OP2-NC-Pad1)") (class "Default")
      (node (ref "OP2") (pin "1") (pinfunction "NC_1") (pintype "passive+no_connect"))
    )
    (net (code "38") (name "unconnected-(OP2-~{PD}-Pad12)") (class "Default")
      (node (ref "OP2") (pin "12") (pinfunction "~{PD}_12") (pintype "input+no_connect"))
    )
  )
)
